# FreeLSSSMDBoard.net
KiCad netlist of a schematic drawn in EAGLE
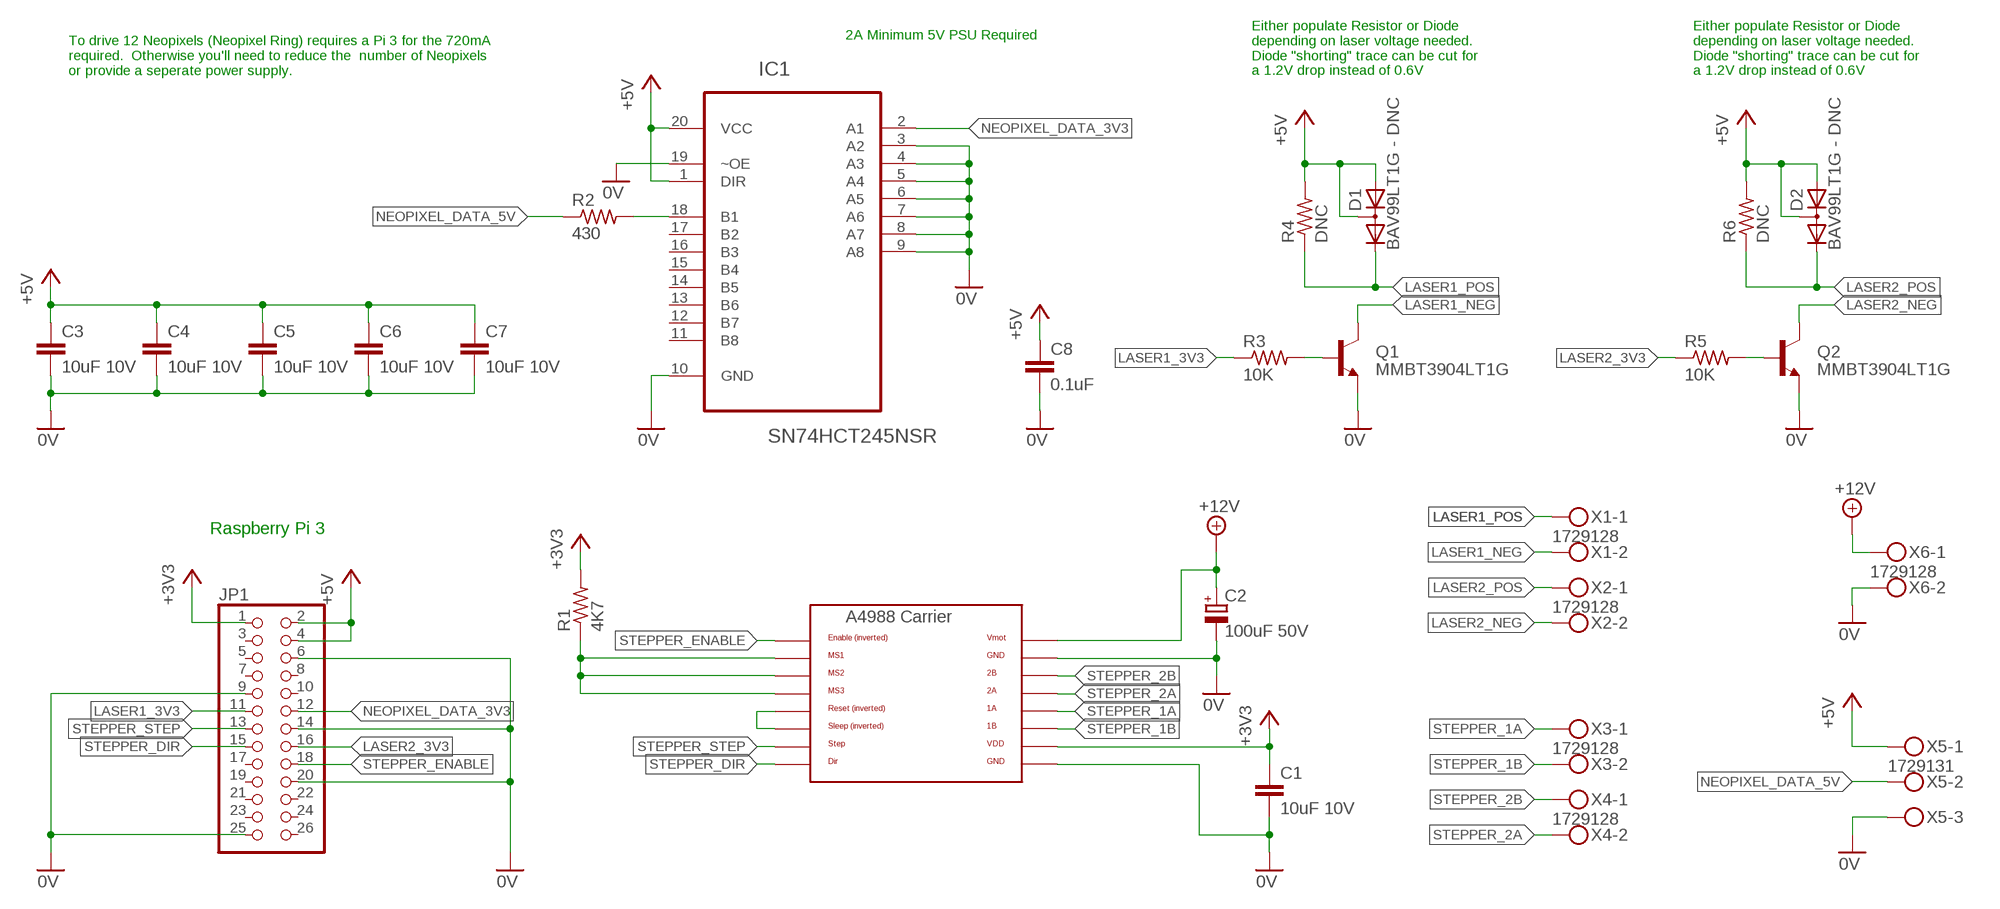
[diagram p0: schematic, sheet 1]

(export (version "E")
  (design (tool "Eeschema 10.0.6"))
  (components
    (comp (ref "C1")
      (value "10uF 10V")
      (footprint "eagle-import:C0603K")
      (libsource (lib "eagle-import") (part "C-EUC0603K"))
    )
    (comp (ref "C2")
      (value "100uF 50V")
      (footprint "eagle-import:E3,5-8")
      (libsource (lib "eagle-import") (part "CPOL-EUE3.5-8"))
    )
    (comp (ref "C3")
      (value "10uF 10V")
      (footprint "eagle-import:C0603K")
      (libsource (lib "eagle-import") (part "C-EUC0603K"))
    )
    (comp (ref "C4")
      (value "10uF 10V")
      (footprint "eagle-import:C0603K")
      (libsource (lib "eagle-import") (part "C-EUC0603K"))
    )
    (comp (ref "C5")
      (value "10uF 10V")
      (footprint "eagle-import:C0603K")
      (libsource (lib "eagle-import") (part "C-EUC0603K"))
    )
    (comp (ref "C6")
      (value "10uF 10V")
      (footprint "eagle-import:C0603K")
      (libsource (lib "eagle-import") (part "C-EUC0603K"))
    )
    (comp (ref "C7")
      (value "10uF 10V")
      (footprint "eagle-import:C0603K")
      (libsource (lib "eagle-import") (part "C-EUC0603K"))
    )
    (comp (ref "C8")
      (value "0.1uF")
      (footprint "eagle-import:C0603K")
      (libsource (lib "eagle-import") (part "C-EUC0603K"))
    )
    (comp (ref "D1")
      (value "BAV99LT1G - DNC")
      (footprint "eagle-import:SOT23")
      (libsource (lib "eagle-import") (part "BAV199"))
    )
    (comp (ref "D2")
      (value "BAV99LT1G - DNC")
      (footprint "eagle-import:SOT23")
      (libsource (lib "eagle-import") (part "BAV199"))
    )
    (comp (ref "IC1")
      (value "SN74HCT245NSR")
      (footprint "eagle-import:SOP-20")
      (libsource (lib "eagle-import") (part "SN74HCT245NSR"))
    )
    (comp (ref "JP1")
      (value "PINHD-2X13")
      (footprint "eagle-import:2X13")
      (libsource (lib "eagle-import") (part "PINHD-2X13"))
    )
    (comp (ref "Q1")
      (value "MMBT3904LT1G")
      (footprint "eagle-import:SOT23-BEC")
      (libsource (lib "eagle-import") (part "MMBT3904LT1G"))
    )
    (comp (ref "Q2")
      (value "MMBT3904LT1G")
      (footprint "eagle-import:SOT23-BEC")
      (libsource (lib "eagle-import") (part "MMBT3904LT1G"))
    )
    (comp (ref "R1")
      (value "4K7")
      (footprint "eagle-import:R0603")
      (libsource (lib "eagle-import") (part "R-US_R0603"))
    )
    (comp (ref "R2")
      (value "430")
      (footprint "eagle-import:R0603")
      (libsource (lib "eagle-import") (part "R-US_R0603"))
    )
    (comp (ref "R3")
      (value "10K")
      (footprint "eagle-import:R0603")
      (libsource (lib "eagle-import") (part "R-US_R0603"))
    )
    (comp (ref "R4")
      (value "DNC")
      (footprint "eagle-import:R0603")
      (libsource (lib "eagle-import") (part "R-US_R0603"))
    )
    (comp (ref "R5")
      (value "10K")
      (footprint "eagle-import:R0603")
      (libsource (lib "eagle-import") (part "R-US_R0603"))
    )
    (comp (ref "R6")
      (value "DNC")
      (footprint "eagle-import:R0603")
      (libsource (lib "eagle-import") (part "R-US_R0603"))
    )
    (comp (ref "U$1")
      (value "A4988BREAKOUT")
      (footprint "eagle-import:A4988BREAKOUT")
      (libsource (lib "eagle-import") (part "A4988BREAKOUT"))
    )
    (comp (ref "X1")
      (value "1729128")
      (footprint "eagle-import:MKDSN1,5_2-5,08")
      (libsource (lib "eagle-import") (part "MKDSN1,5/2-5,08"))
    )
    (comp (ref "X2")
      (value "1729128")
      (footprint "eagle-import:MKDSN1,5_2-5,08")
      (libsource (lib "eagle-import") (part "MKDSN1,5/2-5,08"))
    )
    (comp (ref "X3")
      (value "1729128")
      (footprint "eagle-import:MKDSN1,5_2-5,08")
      (libsource (lib "eagle-import") (part "MKDSN1,5/2-5,08"))
    )
    (comp (ref "X4")
      (value "1729128")
      (footprint "eagle-import:MKDSN1,5_2-5,08")
      (libsource (lib "eagle-import") (part "MKDSN1,5/2-5,08"))
    )
    (comp (ref "X5")
      (value "1729131")
      (footprint "eagle-import:MKDSN1,5_3-5,08")
      (libsource (lib "eagle-import") (part "MKDSN1,5/3-5,08"))
    )
    (comp (ref "X6")
      (value "1729128")
      (footprint "eagle-import:MKDSN1,5_2-5,08")
      (libsource (lib "eagle-import") (part "MKDSN1,5/2-5,08"))
    )
  )
  (nets
    (net (code "1") (name "+3V3") (class "Default")
      (node (ref "C1") (pin "1") (pinfunction "1_1") (pintype "passive"))
      (node (ref "JP1") (pin "1") (pinfunction "1_1") (pintype "passive"))
      (node (ref "R1") (pin "2") (pinfunction "2_2") (pintype "passive"))
      (node (ref "U$1") (pin "VDD") (pinfunction "VDD_VDD") (pintype "power_in"))
    )
    (net (code "2") (name "+5V") (class "Default")
      (node (ref "C3") (pin "1") (pinfunction "1_1") (pintype "passive"))
      (node (ref "C4") (pin "1") (pinfunction "1_1") (pintype "passive"))
      (node (ref "C5") (pin "1") (pinfunction "1_1") (pintype "passive"))
      (node (ref "C6") (pin "1") (pinfunction "1_1") (pintype "passive"))
      (node (ref "C7") (pin "1") (pinfunction "1_1") (pintype "passive"))
      (node (ref "C8") (pin "1") (pinfunction "1_1") (pintype "passive"))
      (node (ref "D1") (pin "1") (pinfunction "A_1") (pintype "passive"))
      (node (ref "D1") (pin "3") (pinfunction "AC_3") (pintype "passive"))
      (node (ref "D2") (pin "1") (pinfunction "A_1") (pintype "passive"))
      (node (ref "D2") (pin "3") (pinfunction "AC_3") (pintype "passive"))
      (node (ref "IC1") (pin "1") (pinfunction "DIR_1") (pintype "input"))
      (node (ref "IC1") (pin "20") (pinfunction "VCC_20") (pintype "power_in"))
      (node (ref "JP1") (pin "2") (pinfunction "2_2") (pintype "passive"))
      (node (ref "JP1") (pin "4") (pinfunction "4_4") (pintype "passive"))
      (node (ref "R4") (pin "2") (pinfunction "2_2") (pintype "passive"))
      (node (ref "R6") (pin "2") (pinfunction "2_2") (pintype "passive"))
      (node (ref "X5") (pin "1") (pinfunction "KL_1") (pintype "passive"))
    )
    (net (code "3") (name "+12V") (class "Default")
      (node (ref "C2") (pin "+") (pinfunction "+_+") (pintype "passive"))
      (node (ref "U$1") (pin "VMOT") (pinfunction "VMOT_VMOT") (pintype "power_in"))
      (node (ref "X6") (pin "1") (pinfunction "KL_1") (pintype "passive"))
    )
    (net (code "4") (name "0V") (class "Default")
      (node (ref "C1") (pin "2") (pinfunction "2_2") (pintype "passive"))
      (node (ref "C2") (pin "-") (pinfunction "-_-") (pintype "passive"))
      (node (ref "C3") (pin "2") (pinfunction "2_2") (pintype "passive"))
      (node (ref "C4") (pin "2") (pinfunction "2_2") (pintype "passive"))
      (node (ref "C5") (pin "2") (pinfunction "2_2") (pintype "passive"))
      (node (ref "C6") (pin "2") (pinfunction "2_2") (pintype "passive"))
      (node (ref "C7") (pin "2") (pinfunction "2_2") (pintype "passive"))
      (node (ref "C8") (pin "2") (pinfunction "2_2") (pintype "passive"))
      (node (ref "IC1") (pin "10") (pinfunction "GND_10") (pintype "passive"))
      (node (ref "IC1") (pin "19") (pinfunction "~{OE}_19") (pintype "input"))
      (node (ref "IC1") (pin "3") (pinfunction "A2_3") (pintype "bidirectional"))
      (node (ref "IC1") (pin "4") (pinfunction "A3_4") (pintype "bidirectional"))
      (node (ref "IC1") (pin "5") (pinfunction "A4_5") (pintype "bidirectional"))
      (node (ref "IC1") (pin "6") (pinfunction "A5_6") (pintype "bidirectional"))
      (node (ref "IC1") (pin "7") (pinfunction "A6_7") (pintype "bidirectional"))
      (node (ref "IC1") (pin "8") (pinfunction "A7_8") (pintype "bidirectional"))
      (node (ref "IC1") (pin "9") (pinfunction "A8_9") (pintype "bidirectional"))
      (node (ref "JP1") (pin "14") (pinfunction "14_14") (pintype "passive"))
      (node (ref "JP1") (pin "20") (pinfunction "20_20") (pintype "passive"))
      (node (ref "JP1") (pin "25") (pinfunction "25_25") (pintype "passive"))
      (node (ref "JP1") (pin "6") (pinfunction "6_6") (pintype "passive"))
      (node (ref "JP1") (pin "9") (pinfunction "9_9") (pintype "passive"))
      (node (ref "Q1") (pin "E") (pinfunction "E_E") (pintype "passive"))
      (node (ref "Q2") (pin "E") (pinfunction "E_E") (pintype "passive"))
      (node (ref "U$1") (pin "GND") (pinfunction "GND_GND") (pintype "power_in"))
      (node (ref "U$1") (pin "GND@0") (pinfunction "GND_GND@0") (pintype "power_in"))
      (node (ref "X5") (pin "3") (pinfunction "KL_3") (pintype "passive"))
      (node (ref "X6") (pin "2") (pinfunction "KL_2") (pintype "passive"))
    )
    (net (code "5") (name "LASER1_3V3") (class "Default")
      (node (ref "JP1") (pin "11") (pinfunction "11_11") (pintype "passive"))
      (node (ref "R3") (pin "1") (pinfunction "1_1") (pintype "passive"))
    )
    (net (code "6") (name "LASER1_NEG") (class "Default")
      (node (ref "Q1") (pin "C") (pinfunction "C_C") (pintype "passive"))
      (node (ref "X1") (pin "2") (pinfunction "KL_2") (pintype "passive"))
    )
    (net (code "7") (name "LASER1_POS") (class "Default")
      (node (ref "D1") (pin "2") (pinfunction "C_2") (pintype "passive"))
      (node (ref "R4") (pin "1") (pinfunction "1_1") (pintype "passive"))
      (node (ref "X1") (pin "1") (pinfunction "KL_1") (pintype "passive"))
    )
    (net (code "8") (name "LASER2_3V3") (class "Default")
      (node (ref "JP1") (pin "16") (pinfunction "16_16") (pintype "passive"))
      (node (ref "R5") (pin "1") (pinfunction "1_1") (pintype "passive"))
    )
    (net (code "9") (name "LASER2_NEG") (class "Default")
      (node (ref "Q2") (pin "C") (pinfunction "C_C") (pintype "passive"))
      (node (ref "X2") (pin "2") (pinfunction "KL_2") (pintype "passive"))
    )
    (net (code "10") (name "LASER2_POS") (class "Default")
      (node (ref "D2") (pin "2") (pinfunction "C_2") (pintype "passive"))
      (node (ref "R6") (pin "1") (pinfunction "1_1") (pintype "passive"))
      (node (ref "X2") (pin "1") (pinfunction "KL_1") (pintype "passive"))
    )
    (net (code "11") (name "NEOPIXEL_DATA_3V3") (class "Default")
      (node (ref "IC1") (pin "2") (pinfunction "A1_2") (pintype "bidirectional"))
      (node (ref "JP1") (pin "12") (pinfunction "12_12") (pintype "passive"))
    )
    (net (code "12") (name "NEOPIXEL_DATA_5V") (class "Default")
      (node (ref "R2") (pin "1") (pinfunction "1_1") (pintype "passive"))
      (node (ref "X5") (pin "2") (pinfunction "KL_2") (pintype "passive"))
    )
    (net (code "13") (name "Net-(IC1-B1)") (class "Default")
      (node (ref "IC1") (pin "18") (pinfunction "B1_18") (pintype "bidirectional"))
      (node (ref "R2") (pin "2") (pinfunction "2_2") (pintype "passive"))
    )
    (net (code "14") (name "Net-(Q1-PadB)") (class "Default")
      (node (ref "Q1") (pin "B") (pinfunction "B_B") (pintype "passive"))
      (node (ref "R3") (pin "2") (pinfunction "2_2") (pintype "passive"))
    )
    (net (code "15") (name "Net-(Q2-PadB)") (class "Default")
      (node (ref "Q2") (pin "B") (pinfunction "B_B") (pintype "passive"))
      (node (ref "R5") (pin "2") (pinfunction "2_2") (pintype "passive"))
    )
    (net (code "16") (name "Net-(R1-Pad1)") (class "Default")
      (node (ref "R1") (pin "1") (pinfunction "1_1") (pintype "passive"))
      (node (ref "U$1") (pin "MS1") (pinfunction "MS1_MS1") (pintype "input"))
      (node (ref "U$1") (pin "MS2") (pinfunction "MS2_MS2") (pintype "input"))
      (node (ref "U$1") (pin "MS3") (pinfunction "MS3_MS3") (pintype "input"))
    )
    (net (code "17") (name "Net-(U$1-SLEEP)") (class "Default")
      (node (ref "U$1") (pin "RST") (pinfunction "RST_RST") (pintype "input"))
      (node (ref "U$1") (pin "SLP") (pinfunction "SLEEP_SLP") (pintype "input"))
    )
    (net (code "18") (name "STEPPER_1A") (class "Default")
      (node (ref "U$1") (pin "1A") (pinfunction "1A_1A") (pintype "output"))
      (node (ref "X3") (pin "1") (pinfunction "KL_1") (pintype "passive"))
    )
    (net (code "19") (name "STEPPER_1B") (class "Default")
      (node (ref "U$1") (pin "1B") (pinfunction "1B_1B") (pintype "output"))
      (node (ref "X3") (pin "2") (pinfunction "KL_2") (pintype "passive"))
    )
    (net (code "20") (name "STEPPER_2A") (class "Default")
      (node (ref "U$1") (pin "2A") (pinfunction "2A_2A") (pintype "output"))
      (node (ref "X4") (pin "2") (pinfunction "KL_2") (pintype "passive"))
    )
    (net (code "21") (name "STEPPER_2B") (class "Default")
      (node (ref "U$1") (pin "2B") (pinfunction "2B_2B") (pintype "output"))
      (node (ref "X4") (pin "1") (pinfunction "KL_1") (pintype "passive"))
    )
    (net (code "22") (name "STEPPER_DIR") (class "Default")
      (node (ref "JP1") (pin "15") (pinfunction "15_15") (pintype "passive"))
      (node (ref "U$1") (pin "DIR") (pinfunction "DIR_DIR") (pintype "input"))
    )
    (net (code "23") (name "STEPPER_ENABLE") (class "Default")
      (node (ref "JP1") (pin "18") (pinfunction "18_18") (pintype "passive"))
      (node (ref "U$1") (pin "EN") (pinfunction "EN_EN") (pintype "input"))
    )
    (net (code "24") (name "STEPPER_STEP") (class "Default")
      (node (ref "JP1") (pin "13") (pinfunction "13_13") (pintype "passive"))
      (node (ref "U$1") (pin "STEP") (pinfunction "STEP_STEP") (pintype "input"))
    )
    (net (code "25") (name "unconnected-(IC1-B2-Pad17)") (class "Default")
      (node (ref "IC1") (pin "17") (pinfunction "B2_17") (pintype "bidirectional"))
    )
    (net (code "26") (name "unconnected-(IC1-B3-Pad16)") (class "Default")
      (node (ref "IC1") (pin "16") (pinfunction "B3_16") (pintype "bidirectional"))
    )
    (net (code "27") (name "unconnected-(IC1-B4-Pad15)") (class "Default")
      (node (ref "IC1") (pin "15") (pinfunction "B4_15") (pintype "bidirectional"))
    )
    (net (code "28") (name "unconnected-(IC1-B5-Pad14)") (class "Default")
      (node (ref "IC1") (pin "14") (pinfunction "B5_14") (pintype "bidirectional"))
    )
    (net (code "29") (name "unconnected-(IC1-B6-Pad13)") (class "Default")
      (node (ref "IC1") (pin "13") (pinfunction "B6_13") (pintype "bidirectional"))
    )
    (net (code "30") (name "unconnected-(IC1-B7-Pad12)") (class "Default")
      (node (ref "IC1") (pin "12") (pinfunction "B7_12") (pintype "bidirectional"))
    )
    (net (code "31") (name "unconnected-(IC1-B8-Pad11)") (class "Default")
      (node (ref "IC1") (pin "11") (pinfunction "B8_11") (pintype "bidirectional"))
    )
    (net (code "32") (name "unconnected-(JP1-Pad3)") (class "Default")
      (node (ref "JP1") (pin "3") (pinfunction "3_3") (pintype "passive"))
    )
    (net (code "33") (name "unconnected-(JP1-Pad5)") (class "Default")
      (node (ref "JP1") (pin "5") (pinfunction "5_5") (pintype "passive"))
    )
    (net (code "34") (name "unconnected-(JP1-Pad7)") (class "Default")
      (node (ref "JP1") (pin "7") (pinfunction "7_7") (pintype "passive"))
    )
    (net (code "35") (name "unconnected-(JP1-Pad8)") (class "Default")
      (node (ref "JP1") (pin "8") (pinfunction "8_8") (pintype "passive"))
    )
    (net (code "36") (name "unconnected-(JP1-Pad10)") (class "Default")
      (node (ref "JP1") (pin "10") (pinfunction "10_10") (pintype "passive"))
    )
    (net (code "37") (name "unconnected-(JP1-Pad17)") (class "Default")
      (node (ref "JP1") (pin "17") (pinfunction "17_17") (pintype "passive"))
    )
    (net (code "38") (name "unconnected-(JP1-Pad19)") (class "Default")
      (node (ref "JP1") (pin "19") (pinfunction "19_19") (pintype "passive"))
    )
    (net (code "39") (name "unconnected-(JP1-Pad21)") (class "Default")
      (node (ref "JP1") (pin "21") (pinfunction "21_21") (pintype "passive"))
    )
    (net (code "40") (name "unconnected-(JP1-Pad22)") (class "Default")
      (node (ref "JP1") (pin "22") (pinfunction "22_22") (pintype "passive"))
    )
    (net (code "41") (name "unconnected-(JP1-Pad23)") (class "Default")
      (node (ref "JP1") (pin "23") (pinfunction "23_23") (pintype "passive"))
    )
    (net (code "42") (name "unconnected-(JP1-Pad24)") (class "Default")
      (node (ref "JP1") (pin "24") (pinfunction "24_24") (pintype "passive"))
    )
    (net (code "43") (name "unconnected-(JP1-Pad26)") (class "Default")
      (node (ref "JP1") (pin "26") (pinfunction "26_26") (pintype "passive"))
    )
  )
)
